# Conectores.net
KiCad netlist of a schematic drawn in Altium Designer
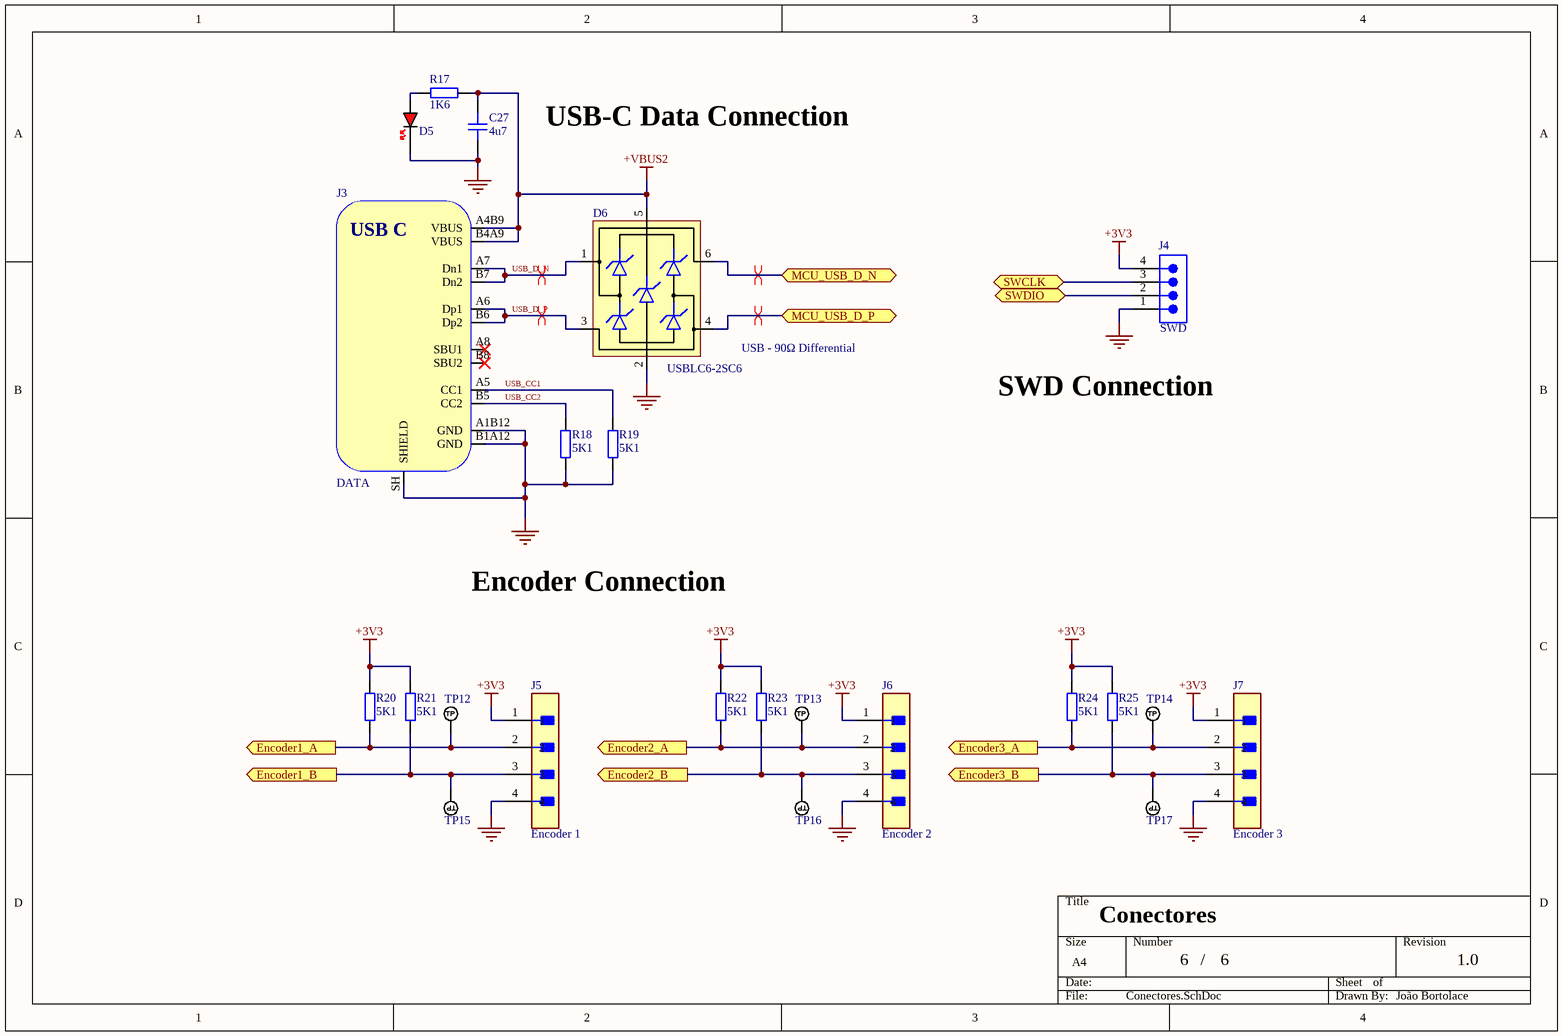
[diagram p0: Conectores.SchDoc]

(export (version "E")
  (design (tool "Eeschema 10.0.6"))
  (components
    (comp (ref "C27")
      (value "4u7")
      (footprint "CAP_0805")
      (description "4.7uF ±10% 50V Ceramic Capacitor X5R 0805")
      (fields
        (field (name "MANUFACTURER") "Samsung Electro-Mechanics")
        (field (name "MANUFACTURER PART NUMBER") "CL21A475KBQNNNE")
      )
      (libsource (lib "Schematic-Lib-PhilsLab") (part "CAP_0805"))
    )
    (comp (ref "D5")
      (value "USB")
      (footprint "LED_0402_RED")
      (description "LED 0402 RED SMD")
      (libsource (lib "Schematic-Lib-PhilsLab") (part "LED_0402_RED"))
    )
    (comp (ref "D6")
      (value "USBLC6-2SC6")
      (footprint "SOT-23-6")
      (description "Low-Capacitance ESD Protection USB")
      (fields (field (name "MANUFACTURER") "STMicroelectronics"))
      (libsource (lib "Schematic-Lib-PhilsLab") (part "USBLC6-2SC6"))
    )
    (comp (ref "J3")
      (value "DATA")
      (footprint "USB4105-GF-A-060")
      (description "USB-C (USB TYPE-C) Receptacle Connector 16 Position Surface Mount, Right Angle")
      (fields
        (field (name "MANUFACTURER") "DEALON")
        (field (name "MANUFACTURER PART NUMBER") "USB-TYPE-C-018")
      )
      (libsource (lib "Schematic-Lib-PhilsLab") (part "USB4105-GF-A-060"))
    )
    (comp (ref "J4")
      (value "SWD")
      (footprint "SMTC-PHT-104-01-X-S")
      (description "Press Fit Header, Through-hole, Vertical, -55 to 125 degC, 2.54 mm Pitch, 4-Pin, Male, RoHS")
      (fields (field (name "MANUFACTURER") "Samtec") (field (name "PARTNUMBER") "PHT-104-01-L-S"))
      (libsource (lib "Altium Content Vault") (part "SMTC-PHT-104-X-X-S-X"))
    )
    (comp (ref "J5")
      (value "Encoder 1")
      (footprint "FP-470531000-MFG")
      (description "CONN HEADER VERT 4POS 2.54MM")
      (libsource (lib "Altium Content Vault") (part "299a8cea1bdcbc3624fe62c390fa72c"))
    )
    (comp (ref "J6")
      (value "Encoder 2")
      (footprint "FP-470531000-MFG")
      (description "CONN HEADER VERT 4POS 2.54MM")
      (libsource (lib "Altium Content Vault") (part "299a8cea1bdcbc3624fe62c390fa72c"))
    )
    (comp (ref "J7")
      (value "Encoder 3")
      (footprint "FP-470531000-MFG")
      (description "CONN HEADER VERT 4POS 2.54MM")
      (libsource (lib "Altium Content Vault") (part "299a8cea1bdcbc3624fe62c390fa72c"))
    )
    (comp (ref "R17")
      (value "1K6")
      (footprint "RES_0402")
      (description "Resistor SMD 0402")
      (libsource (lib "Schematic-Lib-PhilsLab") (part "RES_0402"))
    )
    (comp (ref "R18")
      (value "5K1")
      (footprint "RES_0603")
      (description "Resistor SMD 0603")
      (libsource (lib "Schematic-Lib-PhilsLab") (part "RES_0603"))
    )
    (comp (ref "R19")
      (value "5K1")
      (footprint "RES_0603")
      (description "Resistor SMD 0603")
      (libsource (lib "Schematic-Lib-PhilsLab") (part "RES_0603"))
    )
    (comp (ref "R20")
      (value "5K1")
      (footprint "RES_0402")
      (description "Resistor SMD 0402")
      (libsource (lib "Schematic-Lib-PhilsLab") (part "RES_0402"))
    )
    (comp (ref "R21")
      (value "5K1")
      (footprint "RES_0402")
      (description "Resistor SMD 0402")
      (libsource (lib "Schematic-Lib-PhilsLab") (part "RES_0402"))
    )
    (comp (ref "R22")
      (value "5K1")
      (footprint "RES_0402")
      (description "Resistor SMD 0402")
      (libsource (lib "Schematic-Lib-PhilsLab") (part "RES_0402"))
    )
    (comp (ref "R23")
      (value "5K1")
      (footprint "RES_0402")
      (description "Resistor SMD 0402")
      (libsource (lib "Schematic-Lib-PhilsLab") (part "RES_0402"))
    )
    (comp (ref "R24")
      (value "5K1")
      (footprint "RES_0402")
      (description "Resistor SMD 0402")
      (libsource (lib "Schematic-Lib-PhilsLab") (part "RES_0402"))
    )
    (comp (ref "R25")
      (value "5K1")
      (footprint "RES_0402")
      (description "Resistor SMD 0402")
      (libsource (lib "Schematic-Lib-PhilsLab") (part "RES_0402"))
    )
    (comp (ref "TP12")
      (value "TP_NOBOM")
      (footprint "PAD_RND_1MM")
      (description "Test Point Round 1mm (NO BOM)")
      (libsource (lib "Schematic-Lib-PhilsLab") (part "TEST_POINT_RND_1MM"))
    )
    (comp (ref "TP13")
      (value "TP_NOBOM")
      (footprint "PAD_RND_1MM")
      (description "Test Point Round 1mm (NO BOM)")
      (libsource (lib "Schematic-Lib-PhilsLab") (part "TEST_POINT_RND_1MM"))
    )
    (comp (ref "TP14")
      (value "TP_NOBOM")
      (footprint "PAD_RND_1MM")
      (description "Test Point Round 1mm (NO BOM)")
      (libsource (lib "Schematic-Lib-PhilsLab") (part "TEST_POINT_RND_1MM"))
    )
    (comp (ref "TP15")
      (value "TP_NOBOM")
      (footprint "PAD_RND_1MM")
      (description "Test Point Round 1mm (NO BOM)")
      (libsource (lib "Schematic-Lib-PhilsLab") (part "TEST_POINT_RND_1MM"))
    )
    (comp (ref "TP16")
      (value "TP_NOBOM")
      (footprint "PAD_RND_1MM")
      (description "Test Point Round 1mm (NO BOM)")
      (libsource (lib "Schematic-Lib-PhilsLab") (part "TEST_POINT_RND_1MM"))
    )
    (comp (ref "TP17")
      (value "TP_NOBOM")
      (footprint "PAD_RND_1MM")
      (description "Test Point Round 1mm (NO BOM)")
      (libsource (lib "Schematic-Lib-PhilsLab") (part "TEST_POINT_RND_1MM"))
    )
  )
  (nets
    (net (code "1") (name "+3V3") (class "Default")
      (node (ref "J4") (pin "4") (pinfunction "4_4") (pintype "passive"))
      (node (ref "J5") (pin "1") (pinfunction "1_1") (pintype "passive"))
      (node (ref "J6") (pin "1") (pinfunction "1_1") (pintype "passive"))
      (node (ref "J7") (pin "1") (pinfunction "1_1") (pintype "passive"))
      (node (ref "R20") (pin "2") (pinfunction "2_2") (pintype "passive"))
      (node (ref "R21") (pin "2") (pinfunction "2_2") (pintype "passive"))
      (node (ref "R22") (pin "2") (pinfunction "2_2") (pintype "passive"))
      (node (ref "R23") (pin "2") (pinfunction "2_2") (pintype "passive"))
      (node (ref "R24") (pin "2") (pinfunction "2_2") (pintype "passive"))
      (node (ref "R25") (pin "2") (pinfunction "2_2") (pintype "passive"))
    )
    (net (code "2") (name "+VBUS2") (class "Default")
      (node (ref "C27") (pin "2") (pinfunction "2_2") (pintype "passive"))
      (node (ref "D6") (pin "5") (pinfunction "VBUS_5") (pintype "power_in"))
      (node (ref "J3") (pin "A4B9") (pinfunction "VBUS_A4B9") (pintype "passive"))
      (node (ref "J3") (pin "B4A9") (pinfunction "VBUS_B4A9") (pintype "passive"))
      (node (ref "R17") (pin "2") (pinfunction "2_2") (pintype "passive"))
    )
    (net (code "3") (name "/Encoder1_A") (class "Default")
      (node (ref "J5") (pin "2") (pinfunction "2_2") (pintype "passive"))
      (node (ref "R20") (pin "1") (pinfunction "1_1") (pintype "passive"))
      (node (ref "TP12") (pin "1") (pinfunction "TP_1") (pintype "passive"))
    )
    (net (code "4") (name "/Encoder1_B") (class "Default")
      (node (ref "J5") (pin "3") (pinfunction "3_3") (pintype "passive"))
      (node (ref "R21") (pin "1") (pinfunction "1_1") (pintype "passive"))
      (node (ref "TP15") (pin "1") (pinfunction "TP_1") (pintype "passive"))
    )
    (net (code "5") (name "/Encoder2_A") (class "Default")
      (node (ref "J6") (pin "2") (pinfunction "2_2") (pintype "passive"))
      (node (ref "R22") (pin "1") (pinfunction "1_1") (pintype "passive"))
      (node (ref "TP13") (pin "1") (pinfunction "TP_1") (pintype "passive"))
    )
    (net (code "6") (name "/Encoder2_B") (class "Default")
      (node (ref "J6") (pin "3") (pinfunction "3_3") (pintype "passive"))
      (node (ref "R23") (pin "1") (pinfunction "1_1") (pintype "passive"))
      (node (ref "TP16") (pin "1") (pinfunction "TP_1") (pintype "passive"))
    )
    (net (code "7") (name "/Encoder3_A") (class "Default")
      (node (ref "J7") (pin "2") (pinfunction "2_2") (pintype "passive"))
      (node (ref "R24") (pin "1") (pinfunction "1_1") (pintype "passive"))
      (node (ref "TP14") (pin "1") (pinfunction "TP_1") (pintype "passive"))
    )
    (net (code "8") (name "/Encoder3_B") (class "Default")
      (node (ref "J7") (pin "3") (pinfunction "3_3") (pintype "passive"))
      (node (ref "R25") (pin "1") (pinfunction "1_1") (pintype "passive"))
      (node (ref "TP17") (pin "1") (pinfunction "TP_1") (pintype "passive"))
    )
    (net (code "9") (name "/MCU_USB_D_N") (class "Default")
      (node (ref "D6") (pin "6") (pinfunction "IO1_6") (pintype "bidirectional"))
    )
    (net (code "10") (name "/MCU_USB_D_P") (class "Default")
      (node (ref "D6") (pin "4") (pinfunction "IO2_4") (pintype "bidirectional"))
    )
    (net (code "11") (name "/SWCLK") (class "Default")
      (node (ref "J4") (pin "3") (pinfunction "3_3") (pintype "passive"))
    )
    (net (code "12") (name "/SWDIO") (class "Default")
      (node (ref "J4") (pin "2") (pinfunction "2_2") (pintype "passive"))
    )
    (net (code "13") (name "/USB_CC1") (class "Default")
      (node (ref "J3") (pin "A5") (pinfunction "CC1_A5") (pintype "passive"))
      (node (ref "R19") (pin "2") (pinfunction "2_2") (pintype "passive"))
    )
    (net (code "14") (name "/USB_CC2") (class "Default")
      (node (ref "J3") (pin "B5") (pinfunction "CC2_B5") (pintype "passive"))
      (node (ref "R18") (pin "2") (pinfunction "2_2") (pintype "passive"))
    )
    (net (code "15") (name "/USB_D_N") (class "Default")
      (node (ref "D6") (pin "1") (pinfunction "IO1_1") (pintype "bidirectional"))
      (node (ref "J3") (pin "A7") (pinfunction "Dn1_A7") (pintype "passive"))
      (node (ref "J3") (pin "B7") (pinfunction "Dn2_B7") (pintype "passive"))
    )
    (net (code "16") (name "/USB_D_P") (class "Default")
      (node (ref "D6") (pin "3") (pinfunction "IO2_3") (pintype "bidirectional"))
      (node (ref "J3") (pin "A6") (pinfunction "Dp1_A6") (pintype "passive"))
      (node (ref "J3") (pin "B6") (pinfunction "Dp2_B6") (pintype "passive"))
    )
    (net (code "17") (name "GND") (class "Default")
      (node (ref "C27") (pin "1") (pinfunction "1_1") (pintype "passive"))
      (node (ref "D5") (pin "K") (pinfunction "K_K") (pintype "passive"))
      (node (ref "D6") (pin "2") (pinfunction "GND_2") (pintype "power_in"))
      (node (ref "J3") (pin "A1B12") (pinfunction "GND_A1B12") (pintype "passive"))
      (node (ref "J3") (pin "B1A12") (pinfunction "GND_B1A12") (pintype "passive"))
      (node (ref "J3") (pin "SH") (pinfunction "SHIELD_SH") (pintype "passive"))
      (node (ref "J4") (pin "1") (pinfunction "1_1") (pintype "passive"))
      (node (ref "J5") (pin "4") (pinfunction "4_4") (pintype "passive"))
      (node (ref "J6") (pin "4") (pinfunction "4_4") (pintype "passive"))
      (node (ref "J7") (pin "4") (pinfunction "4_4") (pintype "passive"))
      (node (ref "R18") (pin "1") (pinfunction "1_1") (pintype "passive"))
      (node (ref "R19") (pin "1") (pinfunction "1_1") (pintype "passive"))
    )
    (net (code "18") (name "Net-(D5-PadA)") (class "Default")
      (node (ref "D5") (pin "A") (pinfunction "A_A") (pintype "passive"))
      (node (ref "R17") (pin "1") (pinfunction "1_1") (pintype "passive"))
    )
    (net (code "19") (name "unconnected-(J3-SBU1-PadA8)") (class "Default")
      (node (ref "J3") (pin "A8") (pinfunction "SBU1_A8") (pintype "passive+no_connect"))
    )
    (net (code "20") (name "unconnected-(J3-SBU2-PadB8)") (class "Default")
      (node (ref "J3") (pin "B8") (pinfunction "SBU2_B8") (pintype "passive+no_connect"))
    )
  )
)
